# SCH_PicoPocket_2025-07-21.net
KiCad netlist of a schematic drawn in EasyEDA
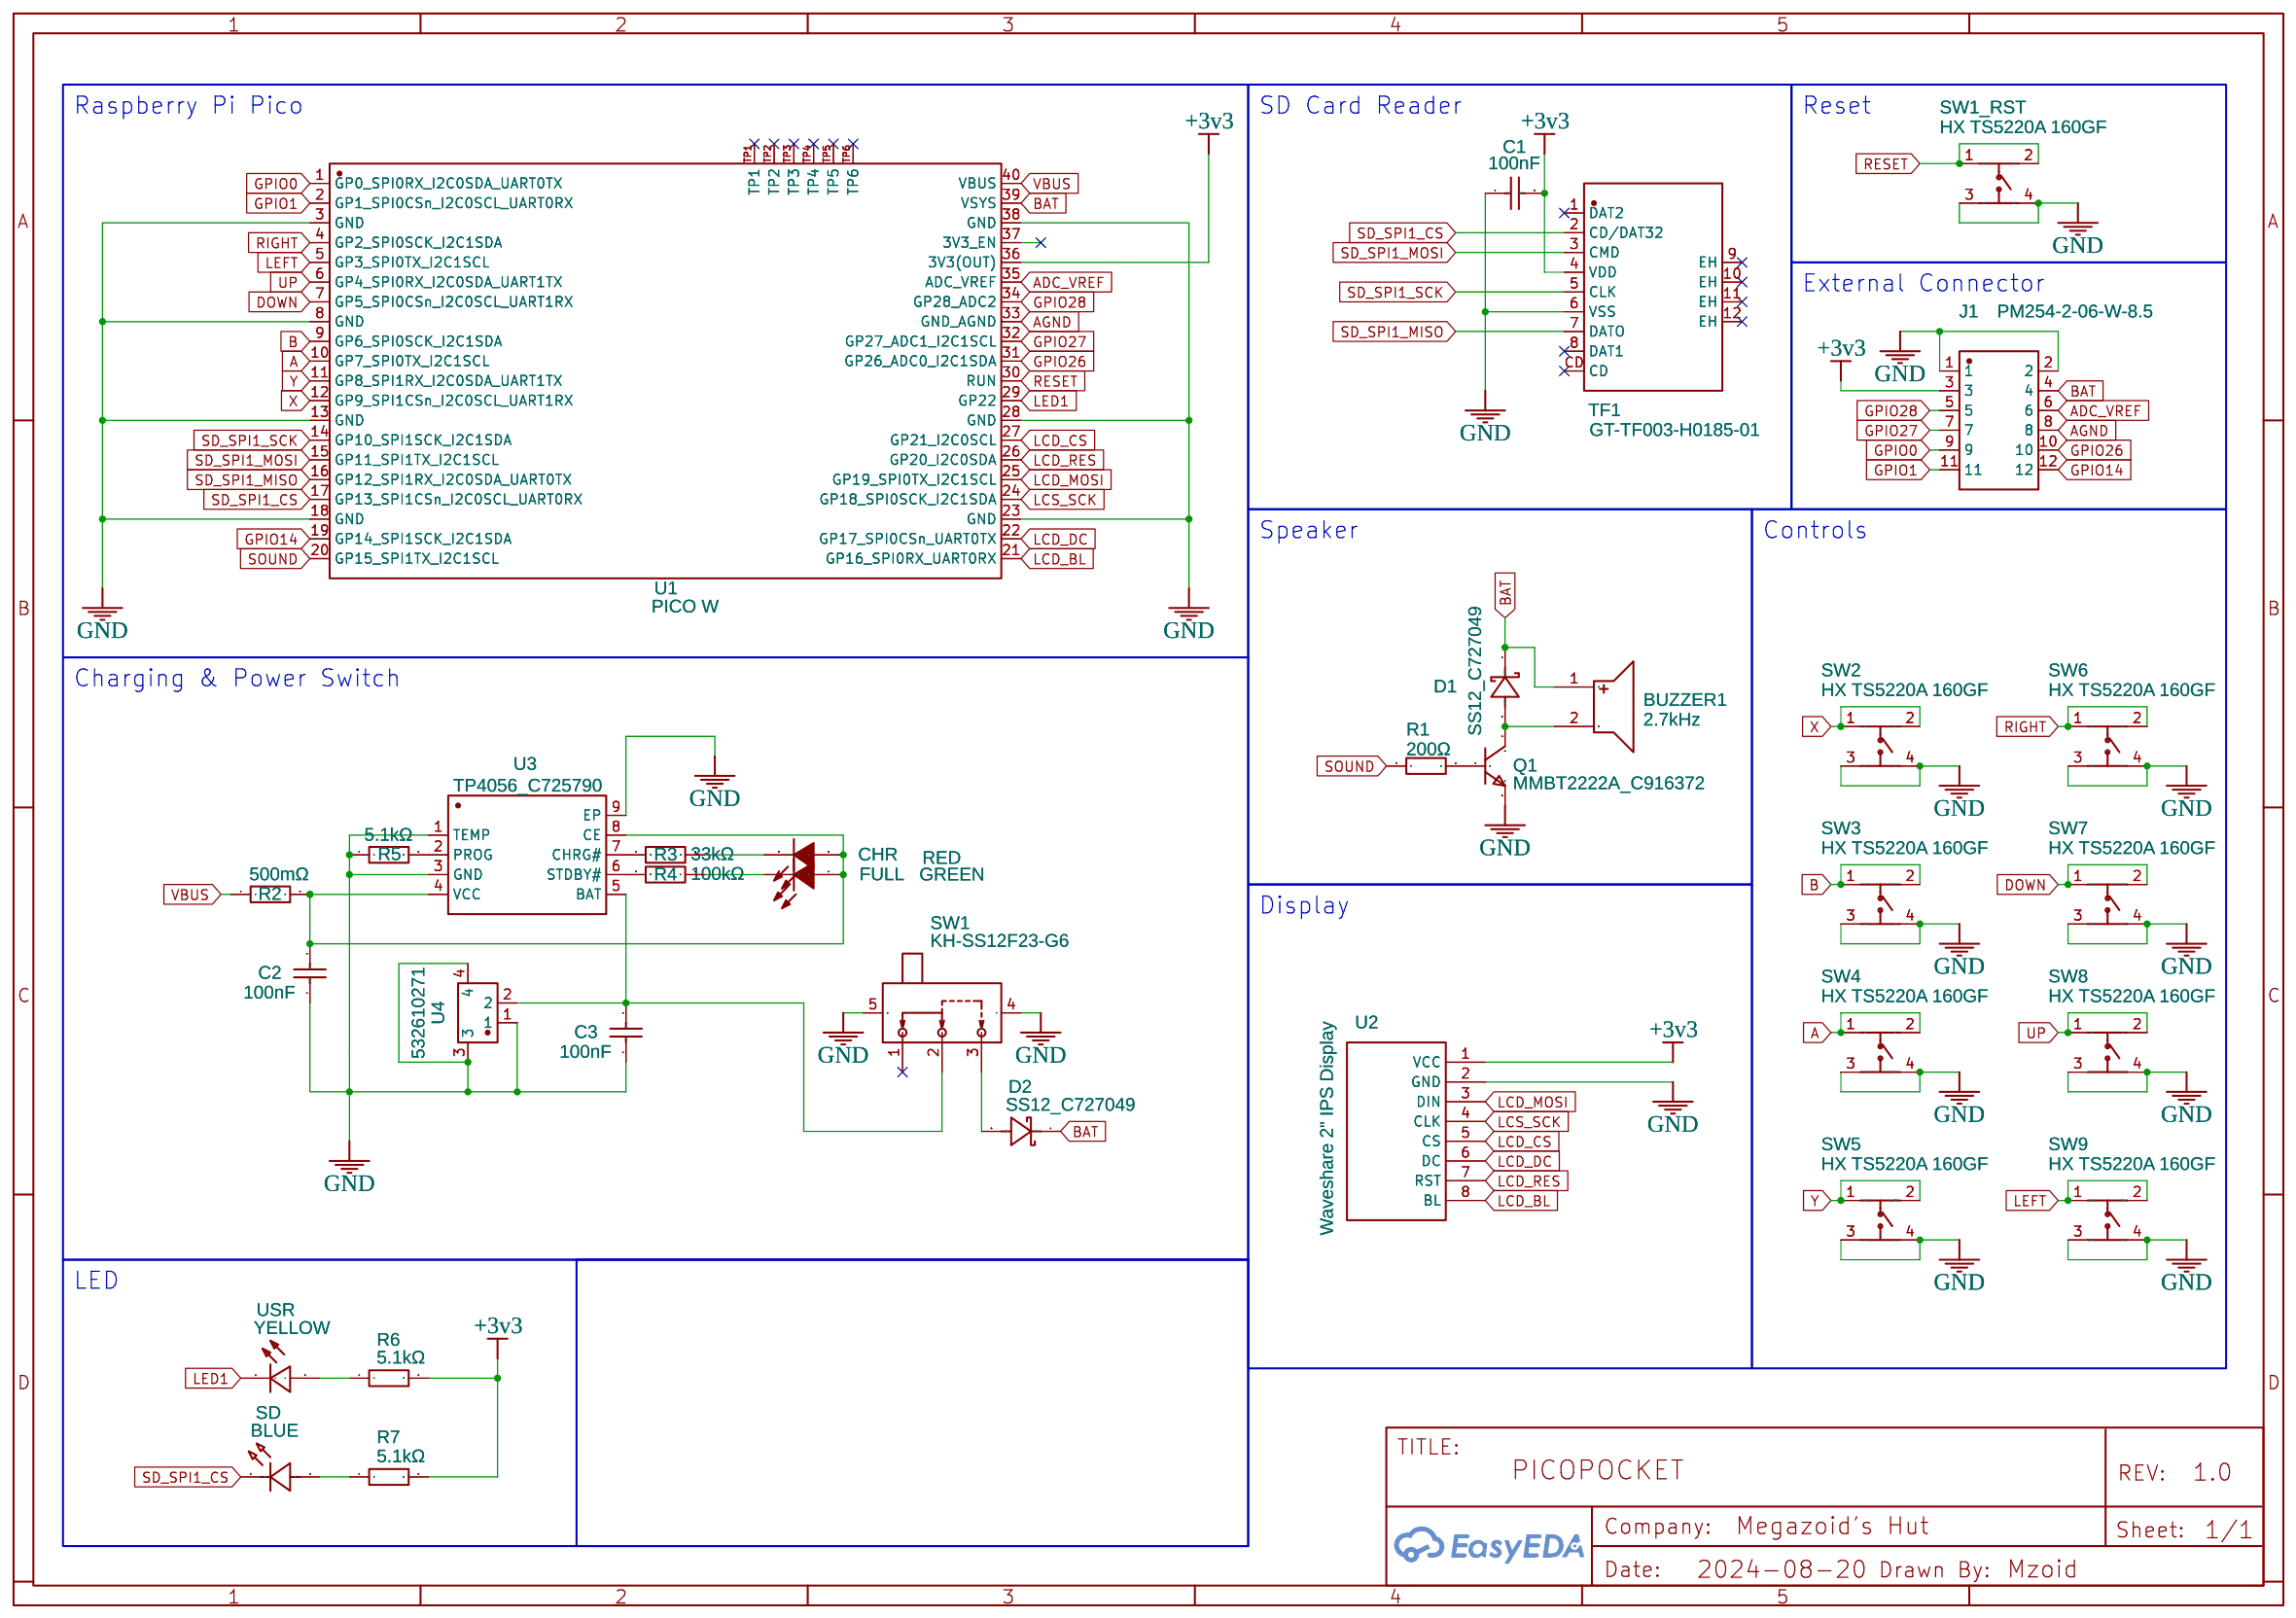
[diagram p0: schematic sheet]

(export (version "E")
  (design (tool "Eeschema 10.0.6"))
  (components
    (comp (ref "BUZZER1")
      (value "2.7kHz")
      (fields (field (name "Manufacturer Part") "FUET-9032-05") (field (name "Manufacturer") "FUET(福声科技)"))
      (libsource (lib "") (part "FUET-9032-05"))
    )
    (comp (ref "C1")
      (value "100nF")
      (fields
        (field (name "Manufacturer Part") "CC0805KRX7R9BB104")
        (field (name "Manufacturer") "YAGEO(国巨)")
      )
      (libsource (lib "") (part "CC0805KRX7R9BB104"))
    )
    (comp (ref "C2")
      (value "100nF")
      (fields
        (field (name "Manufacturer Part") "CC0805KRX7R9BB104")
        (field (name "Manufacturer") "YAGEO(国巨)")
      )
      (libsource (lib "") (part "CC0805KRX7R9BB104_1"))
    )
    (comp (ref "C3")
      (value "100nF")
      (fields
        (field (name "Manufacturer Part") "CC0805KRX7R9BB104")
        (field (name "Manufacturer") "YAGEO(国巨)")
      )
      (libsource (lib "") (part "CC0805KRX7R9BB104_1"))
    )
    (comp (ref "CHR")
      (value "RED")
      (fields (field (name "Manufacturer Part") "LTST-C191KRKT") (field (name "Manufacturer") "LITEON"))
      (libsource (lib "") (part "Unknown_400_-375"))
    )
    (comp (ref "D1")
      (value "SS12_C727049")
      (fields (field (name "Manufacturer Part") "SS12") (field (name "Manufacturer") "TWGMC(台湾迪嘉)"))
      (libsource (lib "") (part "SS12_C727049_1"))
    )
    (comp (ref "D2")
      (value "SS12_C727049")
      (fields (field (name "Manufacturer Part") "SS12") (field (name "Manufacturer") "TWGMC(台湾迪嘉)"))
      (libsource (lib "") (part "SS12_C727049"))
    )
    (comp (ref "FULL")
      (value "GREEN")
      (fields (field (name "Manufacturer Part") "LTST-C193TGKT-5A") (field (name "Manufacturer") "LITEON"))
      (libsource (lib "") (part "Unknown_400_-365"))
    )
    (comp (ref "J1")
      (value "PM254-2-06-W-8.5")
      (fields (field (name "Manufacturer") "HCTL(华灿天禄)"))
      (libsource (lib "") (part "PM254-2-06-W-8.5"))
    )
    (comp (ref "Q1")
      (value "MMBT2222A_C916372")
      (fields (field (name "Manufacturer Part") "MMBT2222A") (field (name "Manufacturer") "JSMSEMI(杰盛微)"))
      (libsource (lib "") (part "MMBT2222A_C916372"))
    )
    (comp (ref "R1")
      (value "200Ω")
      (fields
        (field (name "Manufacturer Part") "0805W8F2000T5E")
        (field (name "Manufacturer") "UNI-ROYAL(厚声)")
      )
      (libsource (lib "") (part "0805W8F2000T5E"))
    )
    (comp (ref "R2")
      (value "500mΩ")
      (fields
        (field (name "Manufacturer Part") "0805W8F500LT5E")
        (field (name "Manufacturer") "UNI-ROYAL(厚声)")
      )
      (libsource (lib "") (part "0805W8F500LT5E"))
    )
    (comp (ref "R3")
      (value "33kΩ")
      (fields
        (field (name "Manufacturer Part") "0603WAF1201T5E")
        (field (name "Manufacturer") "UNI-ROYAL(厚声)")
      )
      (libsource (lib "") (part "0603WAF1201T5E"))
    )
    (comp (ref "R4")
      (value "100kΩ")
      (fields
        (field (name "Manufacturer Part") "0603WAF5101T5E")
        (field (name "Manufacturer") "UNI-ROYAL(厚声)")
      )
      (libsource (lib "") (part "0603WAF5101T5E_1"))
    )
    (comp (ref "R5")
      (value "5.1kΩ")
      (fields
        (field (name "Manufacturer Part") "0603WAF5101T5E")
        (field (name "Manufacturer") "UNI-ROYAL(厚声)")
      )
      (libsource (lib "") (part "0603WAF5101T5E"))
    )
    (comp (ref "R6")
      (value "5.1kΩ")
      (fields
        (field (name "Manufacturer Part") "0603WAF5101T5E")
        (field (name "Manufacturer") "UNI-ROYAL(厚声)")
      )
      (libsource (lib "") (part "0603WAF5101T5E"))
    )
    (comp (ref "R7")
      (value "5.1kΩ")
      (fields
        (field (name "Manufacturer Part") "0603WAF5101T5E")
        (field (name "Manufacturer") "UNI-ROYAL(厚声)")
      )
      (libsource (lib "") (part "0603WAF5101T5E"))
    )
    (comp (ref "SD")
      (value "BLUE")
      (fields (field (name "Manufacturer Part") "LTST-C194TBKT") (field (name "Manufacturer") "LITEON(光宝)"))
      (libsource (lib "") (part "LTST-C194TBKT"))
    )
    (comp (ref "SW1")
      (value "KH-SS12F23-G6")
      (fields (field (name "Manufacturer") "kinghelm(金航标)"))
      (libsource (lib "") (part "KH-SS12F23-G6"))
    )
    (comp (ref "SW1_RST")
      (value "HX TS5220A 160GF")
      (fields
        (field (name "Manufacturer Part") "HX TS5220A 160gf")
        (field (name "Manufacturer") "hanxia(韩下)")
      )
      (libsource (lib "") (part "HX TS5220A 160GF_1"))
    )
    (comp (ref "SW2")
      (value "HX TS5220A 160GF")
      (fields
        (field (name "Manufacturer Part") "HX TS5220A 160gf")
        (field (name "Manufacturer") "hanxia(韩下)")
      )
      (libsource (lib "") (part "HX TS5220A 160GF"))
    )
    (comp (ref "SW3")
      (value "HX TS5220A 160GF")
      (fields
        (field (name "Manufacturer Part") "HX TS5220A 160gf")
        (field (name "Manufacturer") "hanxia(韩下)")
      )
      (libsource (lib "") (part "HX TS5220A 160GF"))
    )
    (comp (ref "SW4")
      (value "HX TS5220A 160GF")
      (fields
        (field (name "Manufacturer Part") "HX TS5220A 160gf")
        (field (name "Manufacturer") "hanxia(韩下)")
      )
      (libsource (lib "") (part "HX TS5220A 160GF"))
    )
    (comp (ref "SW5")
      (value "HX TS5220A 160GF")
      (fields
        (field (name "Manufacturer Part") "HX TS5220A 160gf")
        (field (name "Manufacturer") "hanxia(韩下)")
      )
      (libsource (lib "") (part "HX TS5220A 160GF"))
    )
    (comp (ref "SW6")
      (value "HX TS5220A 160GF")
      (fields
        (field (name "Manufacturer Part") "HX TS5220A 160gf")
        (field (name "Manufacturer") "hanxia(韩下)")
      )
      (libsource (lib "") (part "HX TS5220A 160GF"))
    )
    (comp (ref "SW7")
      (value "HX TS5220A 160GF")
      (fields
        (field (name "Manufacturer Part") "HX TS5220A 160gf")
        (field (name "Manufacturer") "hanxia(韩下)")
      )
      (libsource (lib "") (part "HX TS5220A 160GF"))
    )
    (comp (ref "SW8")
      (value "HX TS5220A 160GF")
      (fields
        (field (name "Manufacturer Part") "HX TS5220A 160gf")
        (field (name "Manufacturer") "hanxia(韩下)")
      )
      (libsource (lib "") (part "HX TS5220A 160GF"))
    )
    (comp (ref "SW9")
      (value "HX TS5220A 160GF")
      (fields
        (field (name "Manufacturer Part") "HX TS5220A 160gf")
        (field (name "Manufacturer") "hanxia(韩下)")
      )
      (libsource (lib "") (part "HX TS5220A 160GF"))
    )
    (comp (ref "TF1")
      (value "GT-TF003-H0185-01")
      (fields (field (name "Manufacturer") "G-Switch(品赞)"))
      (libsource (lib "") (part "GT-TF003-H0185-01"))
    )
    (comp (ref "U1")
      (value "PICO W")
      (fields (field (name "Manufacturer") "Raspberry Pi(树莓派)"))
      (libsource (lib "") (part "PICO W"))
    )
    (comp (ref "U2")
      (value "Waveshare 2\" IPS Display")
      (fields (field (name "Manufacturer Part") "2inch LCD Module") (field (name "Manufacturer") "Waveshare"))
      (libsource (lib "") (part "WAVESHARE 2INCH IPS LCD MODULE"))
    )
    (comp (ref "U3")
      (value "TP4056_C725790")
      (fields (field (name "Manufacturer Part") "TP4056") (field (name "Manufacturer") "UMW(友台半导体)"))
      (libsource (lib "") (part "TP4056_C725790"))
    )
    (comp (ref "U4")
      (value "532610271")
      (fields (field (name "Manufacturer") "MOLEX"))
      (libsource (lib "") (part "532610271_C177225"))
    )
    (comp (ref "USR")
      (value "YELLOW")
      (fields (field (name "Manufacturer Part") "LTST-C190GKT") (field (name "Manufacturer") "LITEON(光宝)"))
      (libsource (lib "") (part "LTST-C190GKT"))
    )
  )
  (nets
    (net (code "1") (name "+3v3") (class "Default")
      (node (ref "C1") (pin "2") (pinfunction "2_2") (pintype "input"))
      (node (ref "J1") (pin "3") (pinfunction "3_3") (pintype "unspecified"))
      (node (ref "R6") (pin "2") (pinfunction "2_2") (pintype "input"))
      (node (ref "R7") (pin "2") (pinfunction "2_2") (pintype "input"))
      (node (ref "TF1") (pin "4") (pinfunction "VDD_4") (pintype "unspecified"))
      (node (ref "U1") (pin "36") (pinfunction "3V3(OUT)_36") (pintype "unspecified"))
      (node (ref "U2") (pin "1") (pinfunction "VCC_1") (pintype "unspecified"))
    )
    (net (code "2") (name "A") (class "Default")
      (node (ref "SW4") (pin "1") (pinfunction "1_1") (pintype "unspecified"))
      (node (ref "SW4") (pin "2") (pinfunction "2_2") (pintype "unspecified"))
      (node (ref "U1") (pin "10") (pinfunction "GP7_SPI0TX_I2C1SCL_10") (pintype "unspecified"))
    )
    (net (code "3") (name "ADC_VREF") (class "Default")
      (node (ref "J1") (pin "6") (pinfunction "6_6") (pintype "unspecified"))
      (node (ref "U1") (pin "35") (pinfunction "ADC_VREF_35") (pintype "unspecified"))
    )
    (net (code "4") (name "AGND") (class "Default")
      (node (ref "J1") (pin "8") (pinfunction "8_8") (pintype "unspecified"))
      (node (ref "U1") (pin "33") (pinfunction "GND_AGND_33") (pintype "unspecified"))
    )
    (net (code "5") (name "B") (class "Default")
      (node (ref "SW3") (pin "1") (pinfunction "1_1") (pintype "unspecified"))
      (node (ref "SW3") (pin "2") (pinfunction "2_2") (pintype "unspecified"))
      (node (ref "U1") (pin "9") (pinfunction "GP6_SPI0SCK_I2C1SDA_9") (pintype "unspecified"))
    )
    (net (code "6") (name "BAT") (class "Default")
      (node (ref "BUZZER1") (pin "1") (pinfunction "1_1") (pintype "unspecified"))
      (node (ref "D1") (pin "1") (pinfunction "1_1") (pintype "unspecified"))
      (node (ref "D2") (pin "1") (pinfunction "1_1") (pintype "unspecified"))
      (node (ref "J1") (pin "4") (pinfunction "4_4") (pintype "unspecified"))
      (node (ref "U1") (pin "39") (pinfunction "VSYS_39") (pintype "unspecified"))
    )
    (net (code "7") (name "DOWN") (class "Default")
      (node (ref "SW7") (pin "1") (pinfunction "1_1") (pintype "unspecified"))
      (node (ref "SW7") (pin "2") (pinfunction "2_2") (pintype "unspecified"))
      (node (ref "U1") (pin "7") (pinfunction "GP5_SPI0CSn_I2C0SCL_UART1RX_7") (pintype "unspecified"))
    )
    (net (code "8") (name "GND") (class "Default")
      (node (ref "C1") (pin "1") (pinfunction "1_1") (pintype "input"))
      (node (ref "C2") (pin "1") (pinfunction "1_1") (pintype "input"))
      (node (ref "C3") (pin "1") (pinfunction "1_1") (pintype "input"))
      (node (ref "J1") (pin "1") (pinfunction "1_1") (pintype "unspecified"))
      (node (ref "J1") (pin "2") (pinfunction "2_2") (pintype "unspecified"))
      (node (ref "Q1") (pin "2") (pinfunction "E_2") (pintype "unspecified"))
      (node (ref "R5") (pin "1") (pinfunction "1_1") (pintype "input"))
      (node (ref "SW1") (pin "4") (pinfunction "4_4") (pintype "unspecified"))
      (node (ref "SW1") (pin "5") (pinfunction "5_5") (pintype "unspecified"))
      (node (ref "SW1_RST") (pin "3") (pinfunction "3_3") (pintype "unspecified"))
      (node (ref "SW1_RST") (pin "4") (pinfunction "4_4") (pintype "unspecified"))
      (node (ref "SW2") (pin "3") (pinfunction "3_3") (pintype "unspecified"))
      (node (ref "SW2") (pin "4") (pinfunction "4_4") (pintype "unspecified"))
      (node (ref "SW3") (pin "3") (pinfunction "3_3") (pintype "unspecified"))
      (node (ref "SW3") (pin "4") (pinfunction "4_4") (pintype "unspecified"))
      (node (ref "SW4") (pin "3") (pinfunction "3_3") (pintype "unspecified"))
      (node (ref "SW4") (pin "4") (pinfunction "4_4") (pintype "unspecified"))
      (node (ref "SW5") (pin "3") (pinfunction "3_3") (pintype "unspecified"))
      (node (ref "SW5") (pin "4") (pinfunction "4_4") (pintype "unspecified"))
      (node (ref "SW6") (pin "3") (pinfunction "3_3") (pintype "unspecified"))
      (node (ref "SW6") (pin "4") (pinfunction "4_4") (pintype "unspecified"))
      (node (ref "SW7") (pin "3") (pinfunction "3_3") (pintype "unspecified"))
      (node (ref "SW7") (pin "4") (pinfunction "4_4") (pintype "unspecified"))
      (node (ref "SW8") (pin "3") (pinfunction "3_3") (pintype "unspecified"))
      (node (ref "SW8") (pin "4") (pinfunction "4_4") (pintype "unspecified"))
      (node (ref "SW9") (pin "3") (pinfunction "3_3") (pintype "unspecified"))
      (node (ref "SW9") (pin "4") (pinfunction "4_4") (pintype "unspecified"))
      (node (ref "TF1") (pin "6") (pinfunction "VSS_6") (pintype "unspecified"))
      (node (ref "U1") (pin "13") (pinfunction "GND_13") (pintype "unspecified"))
      (node (ref "U1") (pin "18") (pinfunction "GND_18") (pintype "unspecified"))
      (node (ref "U1") (pin "23") (pinfunction "GND_23") (pintype "unspecified"))
      (node (ref "U1") (pin "28") (pinfunction "GND_28") (pintype "unspecified"))
      (node (ref "U1") (pin "3") (pinfunction "GND_3") (pintype "unspecified"))
      (node (ref "U1") (pin "38") (pinfunction "GND_38") (pintype "unspecified"))
      (node (ref "U1") (pin "8") (pinfunction "GND_8") (pintype "unspecified"))
      (node (ref "U2") (pin "2") (pinfunction "GND_2") (pintype "unspecified"))
      (node (ref "U3") (pin "1") (pinfunction "TEMP_1") (pintype "unspecified"))
      (node (ref "U3") (pin "3") (pinfunction "GND_3") (pintype "unspecified"))
      (node (ref "U3") (pin "9") (pinfunction "EP_9") (pintype "unspecified"))
      (node (ref "U4") (pin "1") (pinfunction "1_1") (pintype "unspecified"))
      (node (ref "U4") (pin "3") (pinfunction "3_3") (pintype "unspecified"))
      (node (ref "U4") (pin "4") (pinfunction "4_4") (pintype "unspecified"))
    )
    (net (code "9") (name "GPIO0") (class "Default")
      (node (ref "J1") (pin "9") (pinfunction "9_9") (pintype "unspecified"))
      (node (ref "U1") (pin "1") (pinfunction "GP0_SPI0RX_I2C0SDA_UART0TX_1") (pintype "unspecified"))
    )
    (net (code "10") (name "GPIO1") (class "Default")
      (node (ref "J1") (pin "11") (pinfunction "11_11") (pintype "unspecified"))
      (node (ref "U1") (pin "2") (pinfunction "GP1_SPI0CSn_I2C0SCL_UART0RX_2") (pintype "unspecified"))
    )
    (net (code "11") (name "GPIO14") (class "Default")
      (node (ref "J1") (pin "12") (pinfunction "12_12") (pintype "unspecified"))
      (node (ref "U1") (pin "19") (pinfunction "GP14_SPI1SCK_I2C1SDA_19") (pintype "unspecified"))
    )
    (net (code "12") (name "GPIO26") (class "Default")
      (node (ref "J1") (pin "10") (pinfunction "10_10") (pintype "unspecified"))
      (node (ref "U1") (pin "31") (pinfunction "GP26_ADC0_I2C1SDA_31") (pintype "unspecified"))
    )
    (net (code "13") (name "GPIO27") (class "Default")
      (node (ref "J1") (pin "7") (pinfunction "7_7") (pintype "unspecified"))
      (node (ref "U1") (pin "32") (pinfunction "GP27_ADC1_I2C1SCL_32") (pintype "unspecified"))
    )
    (net (code "14") (name "GPIO28") (class "Default")
      (node (ref "J1") (pin "5") (pinfunction "5_5") (pintype "unspecified"))
      (node (ref "U1") (pin "34") (pinfunction "GP28_ADC2_34") (pintype "unspecified"))
    )
    (net (code "15") (name "LCD_BL") (class "Default")
      (node (ref "U1") (pin "21") (pinfunction "GP16_SPI0RX_UART0RX_21") (pintype "unspecified"))
      (node (ref "U2") (pin "8") (pinfunction "BL_8") (pintype "unspecified"))
    )
    (net (code "16") (name "LCD_CS") (class "Default")
      (node (ref "U1") (pin "27") (pinfunction "GP21_I2C0SCL_27") (pintype "unspecified"))
      (node (ref "U2") (pin "5") (pinfunction "CS_5") (pintype "unspecified"))
    )
    (net (code "17") (name "LCD_DC") (class "Default")
      (node (ref "U1") (pin "22") (pinfunction "GP17_SPI0CSn_UART0TX_22") (pintype "unspecified"))
      (node (ref "U2") (pin "6") (pinfunction "DC_6") (pintype "unspecified"))
    )
    (net (code "18") (name "LCD_MOSI") (class "Default")
      (node (ref "U1") (pin "25") (pinfunction "GP19_SPI0TX_I2C1SCL_25") (pintype "unspecified"))
      (node (ref "U2") (pin "3") (pinfunction "DIN_3") (pintype "unspecified"))
    )
    (net (code "19") (name "LCD_RES") (class "Default")
      (node (ref "U1") (pin "26") (pinfunction "GP20_I2C0SDA_26") (pintype "unspecified"))
      (node (ref "U2") (pin "7") (pinfunction "RST_7") (pintype "unspecified"))
    )
    (net (code "20") (name "LCS_SCK") (class "Default")
      (node (ref "U1") (pin "24") (pinfunction "GP18_SPI0SCK_I2C1SDA_24") (pintype "unspecified"))
      (node (ref "U2") (pin "4") (pinfunction "CLK_4") (pintype "unspecified"))
    )
    (net (code "21") (name "LED1") (class "Default")
      (node (ref "U1") (pin "29") (pinfunction "GP22_29") (pintype "unspecified"))
      (node (ref "USR") (pin "1") (pinfunction "-_1") (pintype "unspecified"))
    )
    (net (code "22") (name "LEFT") (class "Default")
      (node (ref "SW9") (pin "1") (pinfunction "1_1") (pintype "unspecified"))
      (node (ref "SW9") (pin "2") (pinfunction "2_2") (pintype "unspecified"))
      (node (ref "U1") (pin "5") (pinfunction "GP3_SPI0TX_I2C1SCL_5") (pintype "unspecified"))
    )
    (net (code "23") (name "Net-(CHR-A)") (class "Default")
      (node (ref "C2") (pin "2") (pinfunction "2_2") (pintype "input"))
      (node (ref "CHR") (pin "1") (pinfunction "A_1") (pintype "unspecified"))
      (node (ref "FULL") (pin "1") (pinfunction "A_1") (pintype "unspecified"))
      (node (ref "R2") (pin "2") (pinfunction "2_2") (pintype "input"))
      (node (ref "U3") (pin "4") (pinfunction "VCC_4") (pintype "unspecified"))
      (node (ref "U3") (pin "8") (pinfunction "CE_8") (pintype "unspecified"))
    )
    (net (code "24") (name "Net-(CHR-K)") (class "Default")
      (node (ref "CHR") (pin "2") (pinfunction "K_2") (pintype "unspecified"))
      (node (ref "R3") (pin "2") (pinfunction "2_2") (pintype "input"))
    )
    (net (code "25") (name "Net-(D2-Pad2)") (class "Default")
      (node (ref "D2") (pin "2") (pinfunction "2_2") (pintype "unspecified"))
      (node (ref "SW1") (pin "3") (pinfunction "3_3") (pintype "unspecified"))
    )
    (net (code "26") (name "Net-(FULL-K)") (class "Default")
      (node (ref "FULL") (pin "2") (pinfunction "K_2") (pintype "unspecified"))
      (node (ref "R4") (pin "1") (pinfunction "1_1") (pintype "input"))
    )
    (net (code "27") (name "Net-(Q1-B)") (class "Default")
      (node (ref "Q1") (pin "1") (pinfunction "B_1") (pintype "unspecified"))
      (node (ref "R1") (pin "2") (pinfunction "2_2") (pintype "input"))
    )
    (net (code "28") (name "Net-(Q1-C)") (class "Default")
      (node (ref "BUZZER1") (pin "2") (pinfunction "2_2") (pintype "unspecified"))
      (node (ref "D1") (pin "2") (pinfunction "2_2") (pintype "unspecified"))
      (node (ref "Q1") (pin "3") (pinfunction "C_3") (pintype "unspecified"))
    )
    (net (code "29") (name "Net-(SD-A)") (class "Default")
      (node (ref "R7") (pin "1") (pinfunction "1_1") (pintype "input"))
      (node (ref "SD") (pin "2") (pinfunction "A_2") (pintype "unspecified"))
    )
    (net (code "30") (name "Net-(U3-BAT)") (class "Default")
      (node (ref "C3") (pin "2") (pinfunction "2_2") (pintype "input"))
      (node (ref "SW1") (pin "2") (pinfunction "2_2") (pintype "unspecified"))
      (node (ref "U3") (pin "5") (pinfunction "BAT_5") (pintype "unspecified"))
      (node (ref "U4") (pin "2") (pinfunction "2_2") (pintype "unspecified"))
    )
    (net (code "31") (name "Net-(U3-CHRG#)") (class "Default")
      (node (ref "R3") (pin "1") (pinfunction "1_1") (pintype "input"))
      (node (ref "U3") (pin "7") (pinfunction "CHRG#_7") (pintype "unspecified"))
    )
    (net (code "32") (name "Net-(U3-PROG)") (class "Default")
      (node (ref "R5") (pin "2") (pinfunction "2_2") (pintype "input"))
      (node (ref "U3") (pin "2") (pinfunction "PROG_2") (pintype "unspecified"))
    )
    (net (code "33") (name "Net-(U3-STDBY#)") (class "Default")
      (node (ref "R4") (pin "2") (pinfunction "2_2") (pintype "input"))
      (node (ref "U3") (pin "6") (pinfunction "STDBY#_6") (pintype "unspecified"))
    )
    (net (code "34") (name "Net-(USR-+)") (class "Default")
      (node (ref "R6") (pin "1") (pinfunction "1_1") (pintype "input"))
      (node (ref "USR") (pin "2") (pinfunction "+_2") (pintype "unspecified"))
    )
    (net (code "35") (name "RESET") (class "Default")
      (node (ref "SW1_RST") (pin "1") (pinfunction "1_1") (pintype "unspecified"))
      (node (ref "SW1_RST") (pin "2") (pinfunction "2_2") (pintype "unspecified"))
      (node (ref "U1") (pin "30") (pinfunction "RUN_30") (pintype "unspecified"))
    )
    (net (code "36") (name "RIGHT") (class "Default")
      (node (ref "SW6") (pin "1") (pinfunction "1_1") (pintype "unspecified"))
      (node (ref "SW6") (pin "2") (pinfunction "2_2") (pintype "unspecified"))
      (node (ref "U1") (pin "4") (pinfunction "GP2_SPI0SCK_I2C1SDA_4") (pintype "unspecified"))
    )
    (net (code "37") (name "SD_SPI1_CS") (class "Default")
      (node (ref "SD") (pin "1") (pinfunction "K_1") (pintype "unspecified"))
      (node (ref "TF1") (pin "2") (pinfunction "CD/DAT32_2") (pintype "unspecified"))
      (node (ref "U1") (pin "17") (pinfunction "GP13_SPI1CSn_I2C0SCL_UART0RX_17") (pintype "unspecified"))
    )
    (net (code "38") (name "SD_SPI1_MISO") (class "Default")
      (node (ref "TF1") (pin "7") (pinfunction "DATO_7") (pintype "unspecified"))
      (node (ref "U1") (pin "16") (pinfunction "GP12_SPI1RX_I2C0SDA_UART0TX_16") (pintype "unspecified"))
    )
    (net (code "39") (name "SD_SPI1_MOSI") (class "Default")
      (node (ref "TF1") (pin "3") (pinfunction "CMD_3") (pintype "unspecified"))
      (node (ref "U1") (pin "15") (pinfunction "GP11_SPI1TX_I2C1SCL_15") (pintype "unspecified"))
    )
    (net (code "40") (name "SD_SPI1_SCK") (class "Default")
      (node (ref "TF1") (pin "5") (pinfunction "CLK_5") (pintype "unspecified"))
      (node (ref "U1") (pin "14") (pinfunction "GP10_SPI1SCK_I2C1SDA_14") (pintype "unspecified"))
    )
    (net (code "41") (name "SOUND") (class "Default")
      (node (ref "R1") (pin "1") (pinfunction "1_1") (pintype "input"))
      (node (ref "U1") (pin "20") (pinfunction "GP15_SPI1TX_I2C1SCL_20") (pintype "unspecified"))
    )
    (net (code "42") (name "UP") (class "Default")
      (node (ref "SW8") (pin "1") (pinfunction "1_1") (pintype "unspecified"))
      (node (ref "SW8") (pin "2") (pinfunction "2_2") (pintype "unspecified"))
      (node (ref "U1") (pin "6") (pinfunction "GP4_SPI0RX_I2C0SDA_UART1TX_6") (pintype "unspecified"))
    )
    (net (code "43") (name "VBUS") (class "Default")
      (node (ref "R2") (pin "1") (pinfunction "1_1") (pintype "input"))
      (node (ref "U1") (pin "40") (pinfunction "VBUS_40") (pintype "unspecified"))
    )
    (net (code "44") (name "X") (class "Default")
      (node (ref "SW2") (pin "1") (pinfunction "1_1") (pintype "unspecified"))
      (node (ref "SW2") (pin "2") (pinfunction "2_2") (pintype "unspecified"))
      (node (ref "U1") (pin "12") (pinfunction "GP9_SPI1CSn_I2C0SCL_UART1RX_12") (pintype "unspecified"))
    )
    (net (code "45") (name "Y") (class "Default")
      (node (ref "SW5") (pin "1") (pinfunction "1_1") (pintype "unspecified"))
      (node (ref "SW5") (pin "2") (pinfunction "2_2") (pintype "unspecified"))
      (node (ref "U1") (pin "11") (pinfunction "GP8_SPI1RX_I2C0SDA_UART1TX_11") (pintype "unspecified"))
    )
    (net (code "46") (name "unconnected-(SW1-Pad1)") (class "Default")
      (node (ref "SW1") (pin "1") (pinfunction "1_1") (pintype "unspecified+no_connect"))
    )
    (net (code "47") (name "unconnected-(TF1-DAT1-Pad8)") (class "Default")
      (node (ref "TF1") (pin "8") (pinfunction "DAT1_8") (pintype "unspecified+no_connect"))
    )
    (net (code "48") (name "unconnected-(TF1-DAT2-Pad1)") (class "Default")
      (node (ref "TF1") (pin "1") (pinfunction "DAT2_1") (pintype "unspecified+no_connect"))
    )
    (net (code "49") (name "unconnected-(TF1-EH-Pad9)") (class "Default")
      (node (ref "TF1") (pin "9") (pinfunction "EH_9") (pintype "unspecified+no_connect"))
    )
    (net (code "50") (name "unconnected-(TF1-EH-Pad10)") (class "Default")
      (node (ref "TF1") (pin "10") (pinfunction "EH_10") (pintype "unspecified+no_connect"))
    )
    (net (code "51") (name "unconnected-(TF1-EH-Pad11)") (class "Default")
      (node (ref "TF1") (pin "11") (pinfunction "EH_11") (pintype "unspecified+no_connect"))
    )
    (net (code "52") (name "unconnected-(TF1-EH-Pad12)") (class "Default")
      (node (ref "TF1") (pin "12") (pinfunction "EH_12") (pintype "unspecified+no_connect"))
    )
    (net (code "53") (name "unconnected-(TF1-PadCD)") (class "Default")
      (node (ref "TF1") (pin "CD") (pinfunction "CD_CD") (pintype "unspecified+no_connect"))
    )
    (net (code "54") (name "unconnected-(U1-3V3_EN-Pad37)") (class "Default")
      (node (ref "U1") (pin "37") (pinfunction "3V3_EN_37") (pintype "unspecified+no_connect"))
    )
    (net (code "55") (name "unconnected-(U1-PadTP1)") (class "Default")
      (node (ref "U1") (pin "TP1") (pinfunction "TP1_TP1") (pintype "unspecified+no_connect"))
    )
    (net (code "56") (name "unconnected-(U1-PadTP2)") (class "Default")
      (node (ref "U1") (pin "TP2") (pinfunction "TP2_TP2") (pintype "unspecified+no_connect"))
    )
    (net (code "57") (name "unconnected-(U1-PadTP3)") (class "Default")
      (node (ref "U1") (pin "TP3") (pinfunction "TP3_TP3") (pintype "unspecified+no_connect"))
    )
    (net (code "58") (name "unconnected-(U1-PadTP4)") (class "Default")
      (node (ref "U1") (pin "TP4") (pinfunction "TP4_TP4") (pintype "unspecified+no_connect"))
    )
    (net (code "59") (name "unconnected-(U1-PadTP5)") (class "Default")
      (node (ref "U1") (pin "TP5") (pinfunction "TP5_TP5") (pintype "unspecified+no_connect"))
    )
    (net (code "60") (name "unconnected-(U1-PadTP6)") (class "Default")
      (node (ref "U1") (pin "TP6") (pinfunction "TP6_TP6") (pintype "unspecified+no_connect"))
    )
  )
)
